# FridgeWarninig_Production.net
KiCad netlist of a schematic drawn in EAGLE
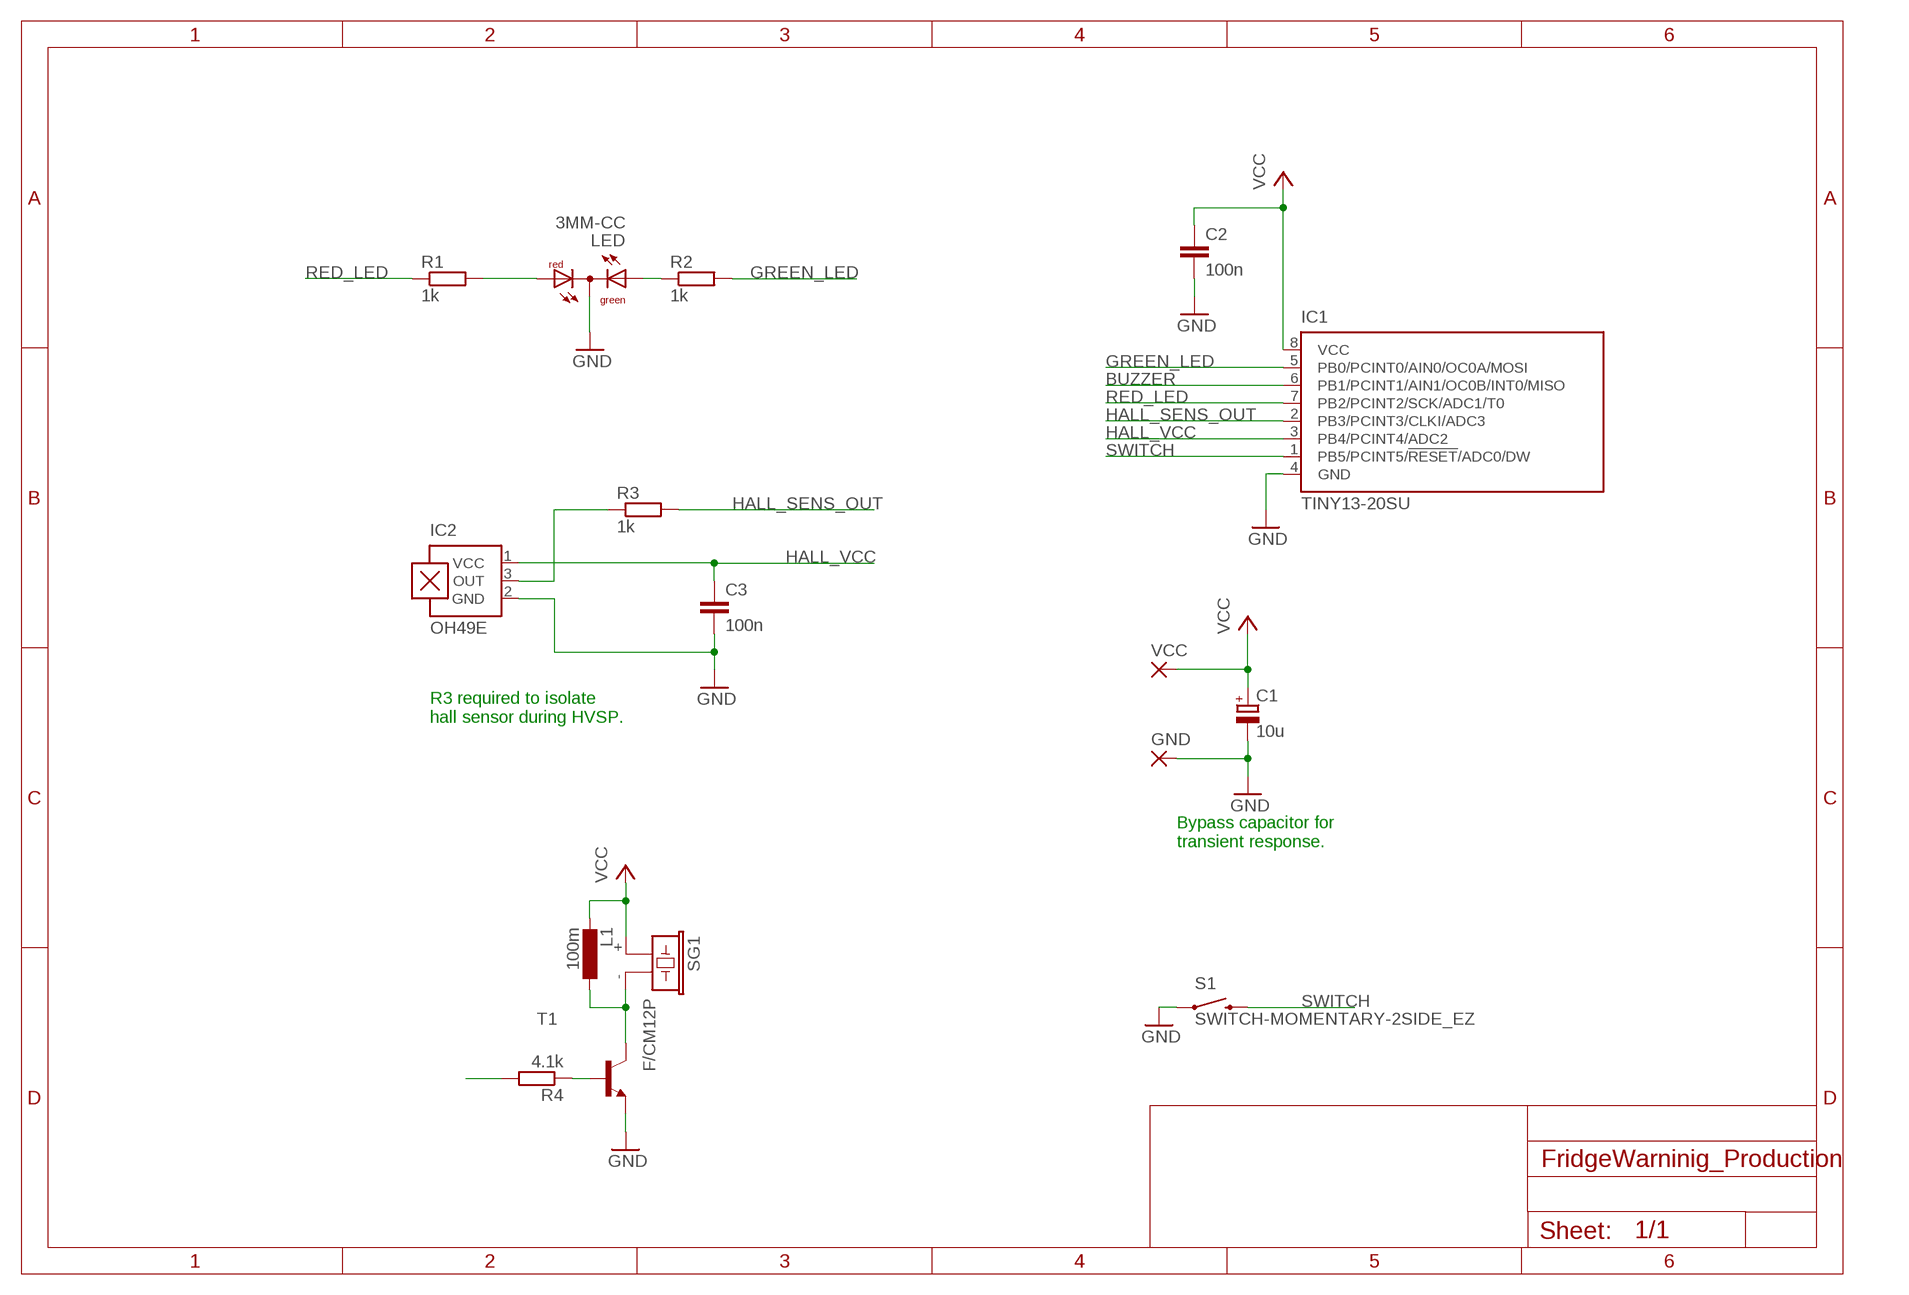
[diagram p0: schematic, sheet 1]

(export (version "E")
  (design (tool "Eeschema 10.0.6"))
  (components
    (comp (ref "C1")
      (value "10u")
      (footprint "eagle-import:153CLV-0405")
      (libsource (lib "eagle-import") (part "CPOL-EU153CLV-0405"))
    )
    (comp (ref "C2")
      (value "100n")
      (footprint "eagle-import:C0603")
      (libsource (lib "eagle-import") (part "C-EUC0603"))
    )
    (comp (ref "C3")
      (value "100n")
      (footprint "eagle-import:C0603")
      (libsource (lib "eagle-import") (part "C-EUC0603"))
    )
    (comp (ref "GND")
      (value "2,54/1,0")
      (footprint "eagle-import:2,54_1,0")
      (libsource (lib "eagle-import") (part "2,54/1,0"))
    )
    (comp (ref "IC1")
      (value "TINY13-20SU")
      (footprint "eagle-import:8S2")
      (fields (field (name "MPN") "ATTINY13-20SU"))
      (libsource (lib "eagle-import") (part "TINY13SU-20"))
    )
    (comp (ref "IC2")
      (value "OH49E")
      (footprint "eagle-import:SIP3-UA")
      (fields (field (name "MF") "ALLEGRO MICROSYSTEMS, INC.") (field (name "MPN") "A1302EUA-T"))
      (libsource (lib "eagle-import") (part "A13?UA02"))
    )
    (comp (ref "L1")
      (value "100m")
      (footprint "eagle-import:TT5D9L")
      (libsource (lib "eagle-import") (part "RADIAL_INDUCTOR_9_12L"))
    )
    (comp (ref "LED")
      (value "3MM-CC")
      (footprint "eagle-import:DUOLED-A-3MM")
      (libsource (lib "eagle-import") (part "3MM-CC"))
    )
    (comp (ref "R1")
      (value "1k")
      (footprint "eagle-import:R0603")
      (libsource (lib "eagle-import") (part "R-EU_R0603"))
    )
    (comp (ref "R2")
      (value "1k")
      (footprint "eagle-import:R0603")
      (libsource (lib "eagle-import") (part "R-EU_R0603"))
    )
    (comp (ref "R3")
      (value "1k")
      (footprint "eagle-import:R0603")
      (libsource (lib "eagle-import") (part "R-EU_R0603"))
    )
    (comp (ref "R4")
      (value "4.1k")
      (footprint "eagle-import:R0603")
      (libsource (lib "eagle-import") (part "R-EU_R0603"))
    )
    (comp (ref "S1")
      (value "SWITCH-MOMENTARY-2SIDE_EZ")
      (footprint "eagle-import:TACTILE-PTH-SIDEEZ")
      (libsource (lib "eagle-import") (part "SWITCH-MOMENTARY-2SIDE_EZ"))
    )
    (comp (ref "SG1")
      (value "F/CM12P")
      (footprint "eagle-import:F_CM12P")
      (libsource (lib "eagle-import") (part "F/CM12P"))
    )
    (comp (ref "T1")
      (value "MMBT918LT1-NPN-SOT23-BEC")
      (footprint "eagle-import:SOT23-BEC")
      (libsource (lib "eagle-import") (part "-NPN-SOT23-BECMMBT918LT1"))
    )
    (comp (ref "VCC")
      (value "2,54/1,0")
      (footprint "eagle-import:2,54_1,0")
      (libsource (lib "eagle-import") (part "2,54/1,0"))
    )
  )
  (nets
    (net (code "1") (name "/BUZZER") (class "Default")
      (node (ref "IC1") (pin "6") (pinfunction "PB1/PCINT1/AIN1/OC0B/INT0/MISO_6") (pintype "bidirectional"))
      (node (ref "R4") (pin "2") (pinfunction "2_2") (pintype "passive"))
    )
    (net (code "2") (name "/GREEN_LED") (class "Default")
      (node (ref "IC1") (pin "5") (pinfunction "PB0/PCINT0/AIN0/OC0A/MOSI_5") (pintype "bidirectional"))
      (node (ref "R2") (pin "2") (pinfunction "2_2") (pintype "passive"))
    )
    (net (code "3") (name "/HALL_SENS_OUT") (class "Default")
      (node (ref "IC1") (pin "2") (pinfunction "PB3/PCINT3/CLKI/ADC3_2") (pintype "bidirectional"))
      (node (ref "R3") (pin "2") (pinfunction "2_2") (pintype "passive"))
    )
    (net (code "4") (name "/HALL_VCC") (class "Default")
      (node (ref "C3") (pin "1") (pinfunction "1_1") (pintype "passive"))
      (node (ref "IC1") (pin "3") (pinfunction "PB4/PCINT4/ADC2_3") (pintype "bidirectional"))
      (node (ref "IC2") (pin "1") (pinfunction "VCC_1") (pintype "power_in"))
    )
    (net (code "5") (name "/RED_LED") (class "Default")
      (node (ref "IC1") (pin "7") (pinfunction "PB2/PCINT2/SCK/ADC1/T0_7") (pintype "bidirectional"))
      (node (ref "R1") (pin "1") (pinfunction "1_1") (pintype "passive"))
    )
    (net (code "6") (name "/SWITCH") (class "Default")
      (node (ref "IC1") (pin "1") (pinfunction "PB5/PCINT5/~{RESET}/ADC0/DW_1") (pintype "bidirectional"))
      (node (ref "S1") (pin "2") (pinfunction "2_2") (pintype "passive"))
    )
    (net (code "7") (name "GND") (class "Default")
      (node (ref "C1") (pin "-") (pinfunction "-_-") (pintype "passive"))
      (node (ref "C2") (pin "2") (pinfunction "2_2") (pintype "passive"))
      (node (ref "C3") (pin "2") (pinfunction "2_2") (pintype "passive"))
      (node (ref "GND") (pin "1") (pinfunction "P_1") (pintype "passive"))
      (node (ref "IC1") (pin "4") (pinfunction "GND_4") (pintype "power_in"))
      (node (ref "IC2") (pin "2") (pinfunction "GND_2") (pintype "power_in"))
      (node (ref "LED") (pin "2") (pinfunction "C_2") (pintype "passive"))
      (node (ref "S1") (pin "1") (pinfunction "1_1") (pintype "passive"))
      (node (ref "T1") (pin "E") (pinfunction "E_E") (pintype "passive"))
    )
    (net (code "8") (name "Net-(IC2-OUT)") (class "Default")
      (node (ref "IC2") (pin "3") (pinfunction "OUT_3") (pintype "output"))
      (node (ref "R3") (pin "1") (pinfunction "1_1") (pintype "passive"))
    )
    (net (code "9") (name "Net-(L1-1)") (class "Default")
      (node (ref "L1") (pin "+") (pinfunction "1_+") (pintype "passive"))
      (node (ref "SG1") (pin "-") (pinfunction "2_-") (pintype "passive"))
      (node (ref "T1") (pin "C") (pinfunction "C_C") (pintype "passive"))
    )
    (net (code "10") (name "Net-(LED-AG)") (class "Default")
      (node (ref "LED") (pin "1") (pinfunction "AG_1") (pintype "passive"))
      (node (ref "R2") (pin "1") (pinfunction "1_1") (pintype "passive"))
    )
    (net (code "11") (name "Net-(LED-AR)") (class "Default")
      (node (ref "LED") (pin "3") (pinfunction "AR_3") (pintype "passive"))
      (node (ref "R1") (pin "2") (pinfunction "2_2") (pintype "passive"))
    )
    (net (code "12") (name "Net-(R4-Pad1)") (class "Default")
      (node (ref "R4") (pin "1") (pinfunction "1_1") (pintype "passive"))
      (node (ref "T1") (pin "B") (pinfunction "B_B") (pintype "passive"))
    )
    (net (code "13") (name "VCC") (class "Default")
      (node (ref "C1") (pin "+") (pinfunction "+_+") (pintype "passive"))
      (node (ref "C2") (pin "1") (pinfunction "1_1") (pintype "passive"))
      (node (ref "IC1") (pin "8") (pinfunction "VCC_8") (pintype "power_in"))
      (node (ref "L1") (pin "-") (pinfunction "2_-") (pintype "passive"))
      (node (ref "SG1") (pin "+") (pinfunction "1_+") (pintype "passive"))
      (node (ref "VCC") (pin "1") (pinfunction "P_1") (pintype "passive"))
    )
  )
)
